# lp50xx-breakout.net
KiCad netlist of a schematic drawn in EAGLE
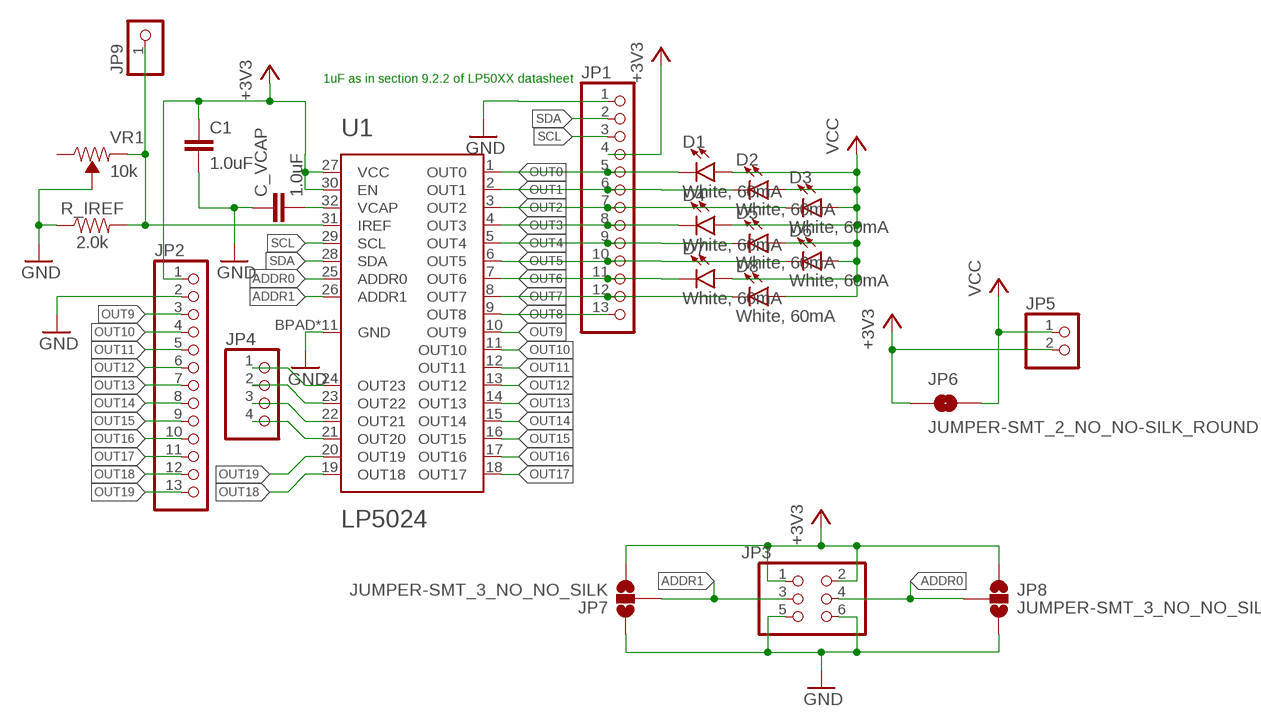
[diagram p0: schematic, sheet 1]

(export (version "E")
  (design (tool "Eeschema 10.0.6"))
  (components
    (comp (ref "C1")
      (value "1.0uF")
      (footprint "eagle-import:0603")
      (libsource (lib "eagle-import") (part "1.0UF-0603-16V-10%"))
    )
    (comp (ref "C_VCAP")
      (value "1.0uF")
      (footprint "eagle-import:0603")
      (libsource (lib "eagle-import") (part "1.0UF-0603-16V-10%"))
    )
    (comp (ref "D1")
      (value "White, 60mA")
      (footprint "eagle-import:SUPER_BRIGHT_SMD_LED_3014")
      (libsource (lib "eagle-import") (part "LED-WHITE3014"))
    )
    (comp (ref "D2")
      (value "White, 60mA")
      (footprint "eagle-import:SUPER_BRIGHT_SMD_LED_3014")
      (libsource (lib "eagle-import") (part "LED-WHITE3014"))
    )
    (comp (ref "D3")
      (value "White, 60mA")
      (footprint "eagle-import:SUPER_BRIGHT_SMD_LED_3014")
      (libsource (lib "eagle-import") (part "LED-WHITE3014"))
    )
    (comp (ref "D4")
      (value "White, 60mA")
      (footprint "eagle-import:SUPER_BRIGHT_SMD_LED_3014")
      (libsource (lib "eagle-import") (part "LED-WHITE3014"))
    )
    (comp (ref "D5")
      (value "White, 60mA")
      (footprint "eagle-import:SUPER_BRIGHT_SMD_LED_3014")
      (libsource (lib "eagle-import") (part "LED-WHITE3014"))
    )
    (comp (ref "D6")
      (value "White, 60mA")
      (footprint "eagle-import:SUPER_BRIGHT_SMD_LED_3014")
      (libsource (lib "eagle-import") (part "LED-WHITE3014"))
    )
    (comp (ref "D7")
      (value "White, 60mA")
      (footprint "eagle-import:SUPER_BRIGHT_SMD_LED_3014")
      (libsource (lib "eagle-import") (part "LED-WHITE3014"))
    )
    (comp (ref "D8")
      (value "White, 60mA")
      (footprint "eagle-import:SUPER_BRIGHT_SMD_LED_3014")
      (libsource (lib "eagle-import") (part "LED-WHITE3014"))
    )
    (comp (ref "JP1")
      (value "PINHD-1X13")
      (footprint "eagle-import:1X13")
      (libsource (lib "eagle-import") (part "PINHD-1X13"))
    )
    (comp (ref "JP2")
      (value "PINHD-1X13")
      (footprint "eagle-import:1X13")
      (libsource (lib "eagle-import") (part "PINHD-1X13"))
    )
    (comp (ref "JP3")
      (value "PINHD-2X3")
      (footprint "eagle-import:2X03")
      (libsource (lib "eagle-import") (part "PINHD-2X3"))
    )
    (comp (ref "JP4")
      (value "PINHD-1X4")
      (footprint "eagle-import:1X04")
      (libsource (lib "eagle-import") (part "PINHD-1X4"))
    )
    (comp (ref "JP5")
      (value "PINHD-1X2")
      (footprint "eagle-import:1X02")
      (libsource (lib "eagle-import") (part "PINHD-1X2"))
    )
    (comp (ref "JP6")
      (value "JUMPER-SMT_2_NO_NO-SILK_ROUND")
      (footprint "eagle-import:SMT-JUMPER_2_NO_NO-SILK_ROUND")
      (libsource (lib "eagle-import") (part "JUMPER-SMT_2_NO_NO-SILK_ROUND"))
    )
    (comp (ref "JP7")
      (value "JUMPER-SMT_3_NO_NO_SILK")
      (footprint "eagle-import:SMT-JUMPER_3_0-NO_TRACE_NO-SILK")
      (libsource (lib "eagle-import") (part "JUMPER-SMT_3_NO_NO_SILK"))
    )
    (comp (ref "JP8")
      (value "JUMPER-SMT_3_NO_NO_SILK")
      (footprint "eagle-import:SMT-JUMPER_3_0-NO_TRACE_NO-SILK")
      (libsource (lib "eagle-import") (part "JUMPER-SMT_3_NO_NO_SILK"))
    )
    (comp (ref "JP9")
      (value "PINHD-1X1")
      (footprint "eagle-import:1X01")
      (libsource (lib "eagle-import") (part "PINHD-1X1"))
    )
    (comp (ref "R_IREF")
      (value "2.0k")
      (footprint "eagle-import:0603")
      (libsource (lib "eagle-import") (part "2.0KOHM-0603-1/10W-5%"))
    )
    (comp (ref "U1")
      (value "LP5024")
      (footprint "eagle-import:S-PVQFN-N32")
      (libsource (lib "eagle-import") (part "LP5024"))
    )
    (comp (ref "VR1")
      (value "10k")
      (footprint "eagle-import:TRIMPOT-SMD-3MM-CLOSED")
      (libsource (lib "eagle-import") (part "TRIMPOT-SMD-3MM-CLOSED-1/8W-20%"))
    )
  )
  (nets
    (net (code "1") (name "+3V3") (class "Default")
      (node (ref "C1") (pin "1") (pinfunction "1_1") (pintype "passive"))
      (node (ref "JP1") (pin "4") (pinfunction "4_4") (pintype "passive"))
      (node (ref "JP2") (pin "1") (pinfunction "1_1") (pintype "passive"))
      (node (ref "JP3") (pin "1") (pinfunction "1_1") (pintype "passive"))
      (node (ref "JP3") (pin "2") (pinfunction "2_2") (pintype "passive"))
      (node (ref "JP5") (pin "2") (pinfunction "2_2") (pintype "passive"))
      (node (ref "JP6") (pin "1") (pinfunction "1_1") (pintype "passive"))
      (node (ref "JP7") (pin "3") (pinfunction "3_3") (pintype "passive"))
      (node (ref "JP8") (pin "1") (pinfunction "1_1") (pintype "passive"))
      (node (ref "U1") (pin "27") (pinfunction "VCC_27") (pintype "bidirectional"))
      (node (ref "U1") (pin "30") (pinfunction "EN_30") (pintype "bidirectional"))
    )
    (net (code "2") (name "ADDR0") (class "Default")
      (node (ref "JP3") (pin "4") (pinfunction "4_4") (pintype "passive"))
      (node (ref "JP8") (pin "2") (pinfunction "2_2") (pintype "passive"))
      (node (ref "U1") (pin "25") (pinfunction "ADDR0_25") (pintype "bidirectional"))
    )
    (net (code "3") (name "ADDR1") (class "Default")
      (node (ref "JP3") (pin "3") (pinfunction "3_3") (pintype "passive"))
      (node (ref "JP7") (pin "2") (pinfunction "2_2") (pintype "passive"))
      (node (ref "U1") (pin "26") (pinfunction "ADDR1_26") (pintype "bidirectional"))
    )
    (net (code "4") (name "GND") (class "Default")
      (node (ref "C1") (pin "2") (pinfunction "2_2") (pintype "passive"))
      (node (ref "C_VCAP") (pin "1") (pinfunction "1_1") (pintype "passive"))
      (node (ref "JP1") (pin "1") (pinfunction "1_1") (pintype "passive"))
      (node (ref "JP2") (pin "2") (pinfunction "2_2") (pintype "passive"))
      (node (ref "JP3") (pin "5") (pinfunction "5_5") (pintype "passive"))
      (node (ref "JP3") (pin "6") (pinfunction "6_6") (pintype "passive"))
      (node (ref "JP7") (pin "1") (pinfunction "1_1") (pintype "passive"))
      (node (ref "JP8") (pin "3") (pinfunction "3_3") (pintype "passive"))
      (node (ref "R_IREF") (pin "1") (pinfunction "1_1") (pintype "passive"))
      (node (ref "U1") (pin "BPAD") (pinfunction "GND_BPAD") (pintype "bidirectional"))
      (node (ref "U1") (pin "EVIA@1") (pinfunction "GND_EVIA@1") (pintype "bidirectional"))
      (node (ref "U1") (pin "EVIA@2") (pinfunction "GND_EVIA@2") (pintype "bidirectional"))
      (node (ref "U1") (pin "EVIA@3") (pinfunction "GND_EVIA@3") (pintype "bidirectional"))
      (node (ref "U1") (pin "EVIA@4") (pinfunction "GND_EVIA@4") (pintype "bidirectional"))
      (node (ref "U1") (pin "EVIA@5") (pinfunction "GND_EVIA@5") (pintype "bidirectional"))
      (node (ref "U1") (pin "EVIA@6") (pinfunction "GND_EVIA@6") (pintype "bidirectional"))
      (node (ref "U1") (pin "EVIA@7") (pinfunction "GND_EVIA@7") (pintype "bidirectional"))
      (node (ref "U1") (pin "EVIA@8") (pinfunction "GND_EVIA@8") (pintype "bidirectional"))
      (node (ref "U1") (pin "EVIA@9") (pinfunction "GND_EVIA@9") (pintype "bidirectional"))
      (node (ref "U1") (pin "TPAD") (pinfunction "GND_TPAD") (pintype "bidirectional"))
      (node (ref "VR1") (pin "2") (pinfunction "WIPER_2") (pintype "passive"))
    )
    (net (code "5") (name "Net-(U1-IREF)") (class "Default")
      (node (ref "JP9") (pin "1") (pinfunction "1_1") (pintype "passive"))
      (node (ref "R_IREF") (pin "2") (pinfunction "2_2") (pintype "passive"))
      (node (ref "U1") (pin "31") (pinfunction "IREF_31") (pintype "bidirectional"))
      (node (ref "VR1") (pin "1") (pinfunction "CCW_1") (pintype "passive"))
    )
    (net (code "6") (name "Net-(U1-OUT20)") (class "Default")
      (node (ref "JP4") (pin "4") (pinfunction "4_4") (pintype "passive"))
      (node (ref "U1") (pin "21") (pinfunction "OUT20_21") (pintype "bidirectional"))
    )
    (net (code "7") (name "Net-(U1-OUT21)") (class "Default")
      (node (ref "JP4") (pin "3") (pinfunction "3_3") (pintype "passive"))
      (node (ref "U1") (pin "22") (pinfunction "OUT21_22") (pintype "bidirectional"))
    )
    (net (code "8") (name "Net-(U1-OUT22)") (class "Default")
      (node (ref "JP4") (pin "2") (pinfunction "2_2") (pintype "passive"))
      (node (ref "U1") (pin "23") (pinfunction "OUT22_23") (pintype "bidirectional"))
    )
    (net (code "9") (name "Net-(U1-OUT23)") (class "Default")
      (node (ref "JP4") (pin "1") (pinfunction "1_1") (pintype "passive"))
      (node (ref "U1") (pin "24") (pinfunction "OUT23_24") (pintype "bidirectional"))
    )
    (net (code "10") (name "Net-(U1-VCAP)") (class "Default")
      (node (ref "C_VCAP") (pin "2") (pinfunction "2_2") (pintype "passive"))
      (node (ref "U1") (pin "32") (pinfunction "VCAP_32") (pintype "bidirectional"))
    )
    (net (code "11") (name "OUT0") (class "Default")
      (node (ref "D1") (pin "C") (pinfunction "C_C") (pintype "passive"))
      (node (ref "JP1") (pin "5") (pinfunction "5_5") (pintype "passive"))
      (node (ref "U1") (pin "1") (pinfunction "OUT0_1") (pintype "bidirectional"))
    )
    (net (code "12") (name "OUT1") (class "Default")
      (node (ref "D2") (pin "C") (pinfunction "C_C") (pintype "passive"))
      (node (ref "JP1") (pin "6") (pinfunction "6_6") (pintype "passive"))
      (node (ref "U1") (pin "2") (pinfunction "OUT1_2") (pintype "bidirectional"))
    )
    (net (code "13") (name "OUT2") (class "Default")
      (node (ref "D3") (pin "C") (pinfunction "C_C") (pintype "passive"))
      (node (ref "JP1") (pin "7") (pinfunction "7_7") (pintype "passive"))
      (node (ref "U1") (pin "3") (pinfunction "OUT2_3") (pintype "bidirectional"))
    )
    (net (code "14") (name "OUT3") (class "Default")
      (node (ref "D4") (pin "C") (pinfunction "C_C") (pintype "passive"))
      (node (ref "JP1") (pin "8") (pinfunction "8_8") (pintype "passive"))
      (node (ref "U1") (pin "4") (pinfunction "OUT3_4") (pintype "bidirectional"))
    )
    (net (code "15") (name "OUT4") (class "Default")
      (node (ref "D5") (pin "C") (pinfunction "C_C") (pintype "passive"))
      (node (ref "JP1") (pin "9") (pinfunction "9_9") (pintype "passive"))
      (node (ref "U1") (pin "5") (pinfunction "OUT4_5") (pintype "bidirectional"))
    )
    (net (code "16") (name "OUT5") (class "Default")
      (node (ref "D6") (pin "C") (pinfunction "C_C") (pintype "passive"))
      (node (ref "JP1") (pin "10") (pinfunction "10_10") (pintype "passive"))
      (node (ref "U1") (pin "6") (pinfunction "OUT5_6") (pintype "bidirectional"))
    )
    (net (code "17") (name "OUT6") (class "Default")
      (node (ref "D7") (pin "C") (pinfunction "C_C") (pintype "passive"))
      (node (ref "JP1") (pin "11") (pinfunction "11_11") (pintype "passive"))
      (node (ref "U1") (pin "7") (pinfunction "OUT6_7") (pintype "bidirectional"))
    )
    (net (code "18") (name "OUT7") (class "Default")
      (node (ref "D8") (pin "C") (pinfunction "C_C") (pintype "passive"))
      (node (ref "JP1") (pin "12") (pinfunction "12_12") (pintype "passive"))
      (node (ref "U1") (pin "8") (pinfunction "OUT7_8") (pintype "bidirectional"))
    )
    (net (code "19") (name "OUT8") (class "Default")
      (node (ref "JP1") (pin "13") (pinfunction "13_13") (pintype "passive"))
      (node (ref "U1") (pin "9") (pinfunction "OUT8_9") (pintype "bidirectional"))
    )
    (net (code "20") (name "OUT9") (class "Default")
      (node (ref "JP2") (pin "3") (pinfunction "3_3") (pintype "passive"))
      (node (ref "U1") (pin "10") (pinfunction "OUT9_10") (pintype "bidirectional"))
    )
    (net (code "21") (name "OUT10") (class "Default")
      (node (ref "JP2") (pin "4") (pinfunction "4_4") (pintype "passive"))
      (node (ref "U1") (pin "11") (pinfunction "OUT10_11") (pintype "bidirectional"))
    )
    (net (code "22") (name "OUT11") (class "Default")
      (node (ref "JP2") (pin "5") (pinfunction "5_5") (pintype "passive"))
      (node (ref "U1") (pin "12") (pinfunction "OUT11_12") (pintype "bidirectional"))
    )
    (net (code "23") (name "OUT12") (class "Default")
      (node (ref "JP2") (pin "6") (pinfunction "6_6") (pintype "passive"))
      (node (ref "U1") (pin "13") (pinfunction "OUT12_13") (pintype "bidirectional"))
    )
    (net (code "24") (name "OUT13") (class "Default")
      (node (ref "JP2") (pin "7") (pinfunction "7_7") (pintype "passive"))
      (node (ref "U1") (pin "14") (pinfunction "OUT13_14") (pintype "bidirectional"))
    )
    (net (code "25") (name "OUT14") (class "Default")
      (node (ref "JP2") (pin "8") (pinfunction "8_8") (pintype "passive"))
      (node (ref "U1") (pin "15") (pinfunction "OUT14_15") (pintype "bidirectional"))
    )
    (net (code "26") (name "OUT15") (class "Default")
      (node (ref "JP2") (pin "9") (pinfunction "9_9") (pintype "passive"))
      (node (ref "U1") (pin "16") (pinfunction "OUT15_16") (pintype "bidirectional"))
    )
    (net (code "27") (name "OUT16") (class "Default")
      (node (ref "JP2") (pin "10") (pinfunction "10_10") (pintype "passive"))
      (node (ref "U1") (pin "17") (pinfunction "OUT16_17") (pintype "bidirectional"))
    )
    (net (code "28") (name "OUT17") (class "Default")
      (node (ref "JP2") (pin "11") (pinfunction "11_11") (pintype "passive"))
      (node (ref "U1") (pin "18") (pinfunction "OUT17_18") (pintype "bidirectional"))
    )
    (net (code "29") (name "OUT18") (class "Default")
      (node (ref "JP2") (pin "12") (pinfunction "12_12") (pintype "passive"))
      (node (ref "U1") (pin "19") (pinfunction "OUT18_19") (pintype "bidirectional"))
    )
    (net (code "30") (name "OUT19") (class "Default")
      (node (ref "JP2") (pin "13") (pinfunction "13_13") (pintype "passive"))
      (node (ref "U1") (pin "20") (pinfunction "OUT19_20") (pintype "bidirectional"))
    )
    (net (code "31") (name "SCL") (class "Default")
      (node (ref "JP1") (pin "3") (pinfunction "3_3") (pintype "passive"))
      (node (ref "U1") (pin "29") (pinfunction "SCL_29") (pintype "bidirectional"))
    )
    (net (code "32") (name "SDA") (class "Default")
      (node (ref "JP1") (pin "2") (pinfunction "2_2") (pintype "passive"))
      (node (ref "U1") (pin "28") (pinfunction "SDA_28") (pintype "bidirectional"))
    )
    (net (code "33") (name "VCC") (class "Default")
      (node (ref "D1") (pin "A") (pinfunction "A_A") (pintype "passive"))
      (node (ref "D2") (pin "A") (pinfunction "A_A") (pintype "passive"))
      (node (ref "D3") (pin "A") (pinfunction "A_A") (pintype "passive"))
      (node (ref "D4") (pin "A") (pinfunction "A_A") (pintype "passive"))
      (node (ref "D5") (pin "A") (pinfunction "A_A") (pintype "passive"))
      (node (ref "D6") (pin "A") (pinfunction "A_A") (pintype "passive"))
      (node (ref "D7") (pin "A") (pinfunction "A_A") (pintype "passive"))
      (node (ref "D8") (pin "A") (pinfunction "A_A") (pintype "passive"))
      (node (ref "JP5") (pin "1") (pinfunction "1_1") (pintype "passive"))
      (node (ref "JP6") (pin "2") (pinfunction "2_2") (pintype "passive"))
    )
    (net (code "34") (name "unconnected-(VR1-CW-Pad3)") (class "Default")
      (node (ref "VR1") (pin "3") (pinfunction "CW_3") (pintype "passive"))
    )
  )
)
